# fdc.net
KiCad netlist of a schematic drawn in Altium Designer
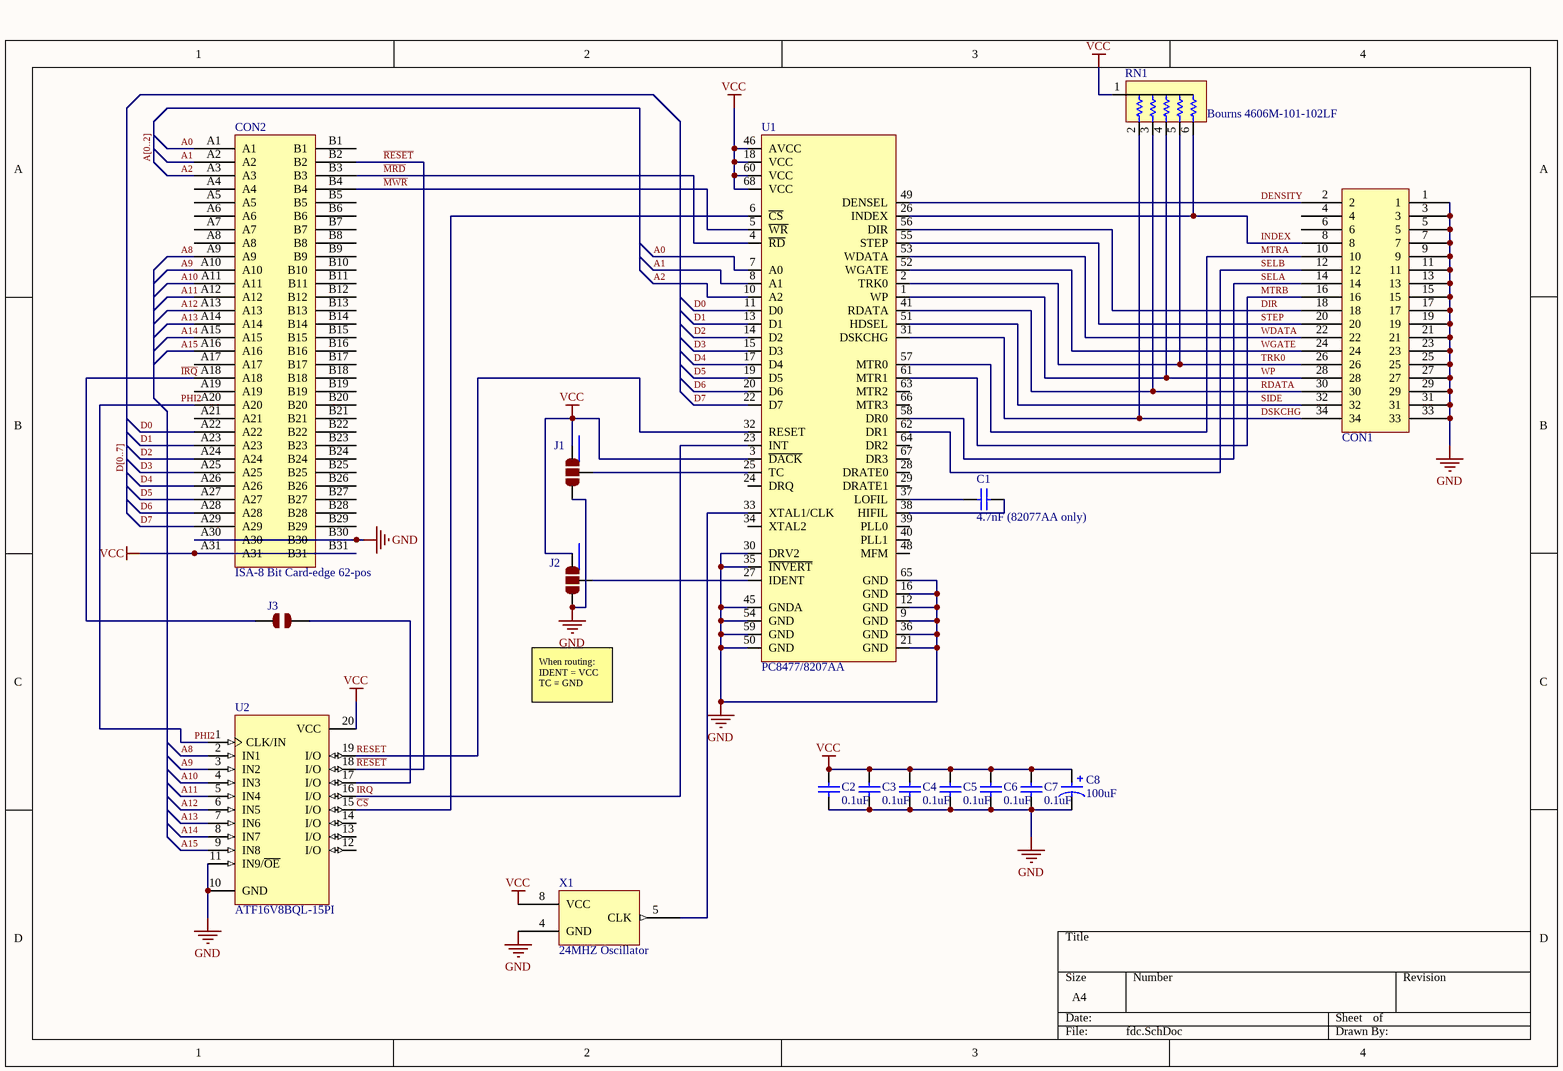
[diagram p0: fdc.SchDoc]

(export (version "E")
  (design (tool "Eeschema 10.0.6"))
  (components
    (comp (ref "C1")
      (value "4.7nF (82077AA only)")
      (footprint "PCB-d10phdktxl02f6vu32bf-1")
      (description "K Series 4.7 nF 50 V ±10 % Tolerance X7R Radial Multilayer Ceramic Capacitor")
      (libsource (lib "CommunityVault") (part "CMP-124134-6"))
    )
    (comp (ref "C2")
      (value "0.1uF")
      (footprint "PCB-gb6o2snpw67z713rrl5r-1")
      (description "Generic Ceramic capacitor")
      (libsource (lib "CommunityVault") (part "CMP-mck1uwszlh1jwp1a4juu-2"))
    )
    (comp (ref "C3")
      (value "0.1uF")
      (footprint "PCB-gb6o2snpw67z713rrl5r-1")
      (description "Generic Ceramic capacitor")
      (libsource (lib "CommunityVault") (part "CMP-mck1uwszlh1jwp1a4juu-2"))
    )
    (comp (ref "C4")
      (value "0.1uF")
      (footprint "PCB-gb6o2snpw67z713rrl5r-1")
      (description "Generic Ceramic capacitor")
      (libsource (lib "CommunityVault") (part "CMP-mck1uwszlh1jwp1a4juu-2"))
    )
    (comp (ref "C5")
      (value "0.1uF")
      (footprint "PCB-gb6o2snpw67z713rrl5r-1")
      (description "Generic Ceramic capacitor")
      (libsource (lib "CommunityVault") (part "CMP-mck1uwszlh1jwp1a4juu-2"))
    )
    (comp (ref "C6")
      (value "0.1uF")
      (footprint "PCB-gb6o2snpw67z713rrl5r-1")
      (description "Generic Ceramic capacitor")
      (libsource (lib "CommunityVault") (part "CMP-mck1uwszlh1jwp1a4juu-2"))
    )
    (comp (ref "C7")
      (value "0.1uF")
      (footprint "PCB-gb6o2snpw67z713rrl5r-1")
      (description "Generic Ceramic capacitor")
      (libsource (lib "CommunityVault") (part "CMP-mck1uwszlh1jwp1a4juu-2"))
    )
    (comp (ref "C8")
      (value "100uF")
      (footprint "PCB-zkzjfh55ek2i5yq9ppya-1")
      (description "Electrolytic capacitor, 2.5mm lead spacing")
      (libsource (lib "FavoritesLibrary") (part "SYM-2ourdj6tgxzh24x23r42-1"))
    )
    (comp (ref "CON1")
      (value "3M N2524-6002RB")
      (footprint "PCB-na3hxtpjg5diai2m4atz-1")
      (description "Header, 4-Wall; Copper Alloy; 200 u in.60/40 Tin/Lead; 2; Black; 0.38 in.; 34")
      (libsource (lib "CommunityVault") (part "CMP-77a2bea8dfe9a865-2"))
    )
    (comp (ref "CON2")
      (value "ISA-8 Bit Card-edge 62-pos")
      (footprint "PCB-2hkdxqdttofatkmr091c-1")
      (description "Card-Edge Male, 62 pos")
      (libsource (lib "CommunityVault") (part "SYM-azy0yq1pw9sh8verv59u-1"))
    )
    (comp (ref "J1")
      (value "Solder Jumper 2-way")
      (footprint "PCB-rrnqmtokqinrd1vbp5jt-1")
      (description "SMD Jumper")
      (libsource (lib "CommunityVault") (part "CMP-0rfjo47dqw9gp5mzow1m-3"))
    )
    (comp (ref "J2")
      (value "Solder Jumper 2-way")
      (footprint "PCB-rrnqmtokqinrd1vbp5jt-1")
      (description "SMD Jumper")
      (libsource (lib "CommunityVault") (part "CMP-0rfjo47dqw9gp5mzow1m-3"))
    )
    (comp (ref "J3")
      (value "SMD Jumper")
      (footprint "PCB-20wha1m7m1debrypqlyx-1")
      (libsource (lib "CommunityVault") (part "SYM-tvx73bcnyo619itupziq-1"))
    )
    (comp (ref "RN1")
      (value "Bourns 4606M-101-102LF")
      (footprint "PCB-6jrb1pmtltsfpt43k1o6-1")
      (description "Res Thick Film NET 1K Ohm 2% 9/10W ±100ppm/°C BUS Conformal 6-Pin SIP Pin Thru-Hole Bulk")
      (fields (field (name "MANUFACTURER PART NUMBER") "4606M-101-102LF"))
      (libsource (lib "FavoritesLibrary") (part "SYM-dbf412e711c10433-1"))
    )
    (comp (ref "U1")
      (value "PC8477/8207AA")
      (footprint "PCB-89xdsse3ufb116eei8ku-1")
      (description "IC Advanced Floppy Ctrlr 68PLCC")
      (libsource (lib "CommunityVault") (part "CMP-e29e2b93411d3d59-3"))
    )
    (comp (ref "U2")
      (value "ATF16V8BQL-15PI")
      (footprint "20P3")
      (description "ATF16V8BQL 5.0V Industry Standard SPLD, 20-lead PDIP, Speed Grade 15, Industrial Grade")
      (libsource (lib "CommunityVault") (part "PLD-ATSPLD-16V8B-IL20"))
    )
    (comp (ref "X1")
      (value "24MHZ Oscillator")
      (footprint "PCB-38wfzuzk5mkmrw5gxtuy-1")
      (description "Generic footprint for Dip-8 Can Oscillator")
      (libsource (lib "FavoritesLibrary") (part "SYM-5f5w4rnabuyvhbl8pua9-1"))
    )
  )
  (nets
    (net (code "1") (name "/A0") (class "Default")
      (node (ref "CON2") (pin "A1") (pinfunction "A1_A1") (pintype "passive"))
      (node (ref "U1") (pin "7") (pinfunction "A0_7") (pintype "passive"))
    )
    (net (code "2") (name "/A1") (class "Default")
      (node (ref "CON2") (pin "A2") (pinfunction "A2_A2") (pintype "passive"))
      (node (ref "U1") (pin "8") (pinfunction "A1_8") (pintype "passive"))
    )
    (net (code "3") (name "/A2") (class "Default")
      (node (ref "CON2") (pin "A3") (pinfunction "A3_A3") (pintype "passive"))
      (node (ref "U1") (pin "10") (pinfunction "A2_10") (pintype "passive"))
    )
    (net (code "4") (name "/A8") (class "Default")
      (node (ref "CON2") (pin "A9") (pinfunction "A9_A9") (pintype "passive"))
      (node (ref "U2") (pin "2") (pinfunction "IN1_2") (pintype "input"))
    )
    (net (code "5") (name "/A9") (class "Default")
      (node (ref "CON2") (pin "A10") (pinfunction "A10_A10") (pintype "passive"))
      (node (ref "U2") (pin "3") (pinfunction "IN2_3") (pintype "input"))
    )
    (net (code "6") (name "/A10") (class "Default")
      (node (ref "CON2") (pin "A11") (pinfunction "A11_A11") (pintype "passive"))
      (node (ref "U2") (pin "4") (pinfunction "IN3_4") (pintype "input"))
    )
    (net (code "7") (name "/A11") (class "Default")
      (node (ref "CON2") (pin "A12") (pinfunction "A12_A12") (pintype "passive"))
      (node (ref "U2") (pin "5") (pinfunction "IN4_5") (pintype "input"))
    )
    (net (code "8") (name "/A12") (class "Default")
      (node (ref "CON2") (pin "A13") (pinfunction "A13_A13") (pintype "passive"))
      (node (ref "U2") (pin "6") (pinfunction "IN5_6") (pintype "input"))
    )
    (net (code "9") (name "/A13") (class "Default")
      (node (ref "CON2") (pin "A14") (pinfunction "A14_A14") (pintype "passive"))
      (node (ref "U2") (pin "7") (pinfunction "IN6_7") (pintype "input"))
    )
    (net (code "10") (name "/A14") (class "Default")
      (node (ref "CON2") (pin "A15") (pinfunction "A15_A15") (pintype "passive"))
      (node (ref "U2") (pin "8") (pinfunction "IN7_8") (pintype "input"))
    )
    (net (code "11") (name "/A15") (class "Default")
      (node (ref "CON2") (pin "A16") (pinfunction "A16_A16") (pintype "passive"))
      (node (ref "U2") (pin "9") (pinfunction "IN8_9") (pintype "input"))
    )
    (net (code "13") (name "/D0") (class "Default")
      (node (ref "CON2") (pin "A22") (pinfunction "A22_A22") (pintype "passive"))
      (node (ref "U1") (pin "11") (pinfunction "D0_11") (pintype "passive"))
    )
    (net (code "14") (name "/D1") (class "Default")
      (node (ref "CON2") (pin "A23") (pinfunction "A23_A23") (pintype "passive"))
      (node (ref "U1") (pin "13") (pinfunction "D1_13") (pintype "passive"))
    )
    (net (code "15") (name "/D2") (class "Default")
      (node (ref "CON2") (pin "A24") (pinfunction "A24_A24") (pintype "passive"))
      (node (ref "U1") (pin "14") (pinfunction "D2_14") (pintype "passive"))
    )
    (net (code "16") (name "/D3") (class "Default")
      (node (ref "CON2") (pin "A25") (pinfunction "A25_A25") (pintype "passive"))
      (node (ref "U1") (pin "15") (pinfunction "D3_15") (pintype "passive"))
    )
    (net (code "17") (name "/D4") (class "Default")
      (node (ref "CON2") (pin "A26") (pinfunction "A26_A26") (pintype "passive"))
      (node (ref "U1") (pin "17") (pinfunction "D4_17") (pintype "passive"))
    )
    (net (code "18") (name "/D5") (class "Default")
      (node (ref "CON2") (pin "A27") (pinfunction "A27_A27") (pintype "passive"))
      (node (ref "U1") (pin "19") (pinfunction "D5_19") (pintype "passive"))
    )
    (net (code "19") (name "/D6") (class "Default")
      (node (ref "CON2") (pin "A28") (pinfunction "A28_A28") (pintype "passive"))
      (node (ref "U1") (pin "20") (pinfunction "D6_20") (pintype "passive"))
    )
    (net (code "20") (name "/D7") (class "Default")
      (node (ref "CON2") (pin "A29") (pinfunction "A29_A29") (pintype "passive"))
      (node (ref "U1") (pin "22") (pinfunction "D7_22") (pintype "passive"))
    )
    (net (code "21") (name "/DENSITY") (class "Default")
      (node (ref "CON1") (pin "2") (pinfunction "2_2") (pintype "passive"))
      (node (ref "U1") (pin "49") (pinfunction "DENSEL_49") (pintype "passive"))
    )
    (net (code "22") (name "/DIR") (class "Default")
      (node (ref "CON1") (pin "18") (pinfunction "18_18") (pintype "passive"))
      (node (ref "U1") (pin "56") (pinfunction "DIR_56") (pintype "passive"))
    )
    (net (code "23") (name "/DSKCHG") (class "Default")
      (node (ref "CON1") (pin "34") (pinfunction "34_34") (pintype "passive"))
      (node (ref "RN1") (pin "2") (pinfunction "2_2") (pintype "passive"))
      (node (ref "U1") (pin "31") (pinfunction "DSKCHG_31") (pintype "passive"))
    )
    (net (code "25") (name "/INDEX") (class "Default")
      (node (ref "CON1") (pin "8") (pinfunction "8_8") (pintype "passive"))
      (node (ref "RN1") (pin "6") (pinfunction "6_6") (pintype "passive"))
      (node (ref "U1") (pin "26") (pinfunction "INDEX_26") (pintype "passive"))
    )
    (net (code "26") (name "/IRQ") (class "Default")
      (node (ref "U1") (pin "23") (pinfunction "INT_23") (pintype "passive"))
      (node (ref "U2") (pin "16") (pinfunction "I/O_16") (pintype "bidirectional"))
    )
    (net (code "27") (name "/MTRA") (class "Default")
      (node (ref "CON1") (pin "10") (pinfunction "10_10") (pintype "passive"))
      (node (ref "U1") (pin "57") (pinfunction "MTR0_57") (pintype "passive"))
    )
    (net (code "28") (name "/MTRB") (class "Default")
      (node (ref "CON1") (pin "16") (pinfunction "16_16") (pintype "passive"))
      (node (ref "U1") (pin "61") (pinfunction "MTR1_61") (pintype "passive"))
    )
    (net (code "29") (name "/PHI2") (class "Default")
      (node (ref "CON2") (pin "A20") (pinfunction "A20_A20") (pintype "passive"))
      (node (ref "U2") (pin "1") (pinfunction "CLK/IN_1") (pintype "input"))
    )
    (net (code "30") (name "/RDATA") (class "Default")
      (node (ref "CON1") (pin "30") (pinfunction "30_30") (pintype "passive"))
      (node (ref "RN1") (pin "3") (pinfunction "3_3") (pintype "passive"))
      (node (ref "U1") (pin "41") (pinfunction "RDATA_41") (pintype "passive"))
    )
    (net (code "31") (name "/RESET") (class "Default")
      (node (ref "U1") (pin "32") (pinfunction "RESET_32") (pintype "passive"))
      (node (ref "U2") (pin "19") (pinfunction "I/O_19") (pintype "bidirectional"))
    )
    (net (code "32") (name "/SELA") (class "Default")
      (node (ref "CON1") (pin "14") (pinfunction "14_14") (pintype "passive"))
      (node (ref "U1") (pin "58") (pinfunction "DR0_58") (pintype "passive"))
    )
    (net (code "33") (name "/SELB") (class "Default")
      (node (ref "CON1") (pin "12") (pinfunction "12_12") (pintype "passive"))
      (node (ref "U1") (pin "62") (pinfunction "DR1_62") (pintype "passive"))
    )
    (net (code "34") (name "/SIDE") (class "Default")
      (node (ref "CON1") (pin "32") (pinfunction "32_32") (pintype "passive"))
      (node (ref "U1") (pin "51") (pinfunction "HDSEL_51") (pintype "passive"))
    )
    (net (code "35") (name "/STEP") (class "Default")
      (node (ref "CON1") (pin "20") (pinfunction "20_20") (pintype "passive"))
      (node (ref "U1") (pin "55") (pinfunction "STEP_55") (pintype "passive"))
    )
    (net (code "36") (name "/TRK0") (class "Default")
      (node (ref "CON1") (pin "26") (pinfunction "26_26") (pintype "passive"))
      (node (ref "RN1") (pin "5") (pinfunction "5_5") (pintype "passive"))
      (node (ref "U1") (pin "2") (pinfunction "TRK0_2") (pintype "passive"))
    )
    (net (code "37") (name "/WDATA") (class "Default")
      (node (ref "CON1") (pin "22") (pinfunction "22_22") (pintype "passive"))
      (node (ref "U1") (pin "53") (pinfunction "WDATA_53") (pintype "passive"))
    )
    (net (code "38") (name "/WGATE") (class "Default")
      (node (ref "CON1") (pin "24") (pinfunction "24_24") (pintype "passive"))
      (node (ref "U1") (pin "52") (pinfunction "WGATE_52") (pintype "passive"))
    )
    (net (code "39") (name "/WP") (class "Default")
      (node (ref "CON1") (pin "28") (pinfunction "28_28") (pintype "passive"))
      (node (ref "RN1") (pin "4") (pinfunction "4_4") (pintype "passive"))
      (node (ref "U1") (pin "1") (pinfunction "WP_1") (pintype "passive"))
    )
    (net (code "40") (name "/~{CS}") (class "Default")
      (node (ref "U1") (pin "6") (pinfunction "~{CS}_6") (pintype "passive"))
      (node (ref "U2") (pin "15") (pinfunction "I/O_15") (pintype "bidirectional"))
    )
    (net (code "41") (name "/~{IRQ}") (class "Default")
      (node (ref "CON2") (pin "A18") (pinfunction "A18_A18") (pintype "passive"))
      (node (ref "J3") (pin "1") (pinfunction "1_1") (pintype "passive"))
    )
    (net (code "42") (name "/~{MRD}") (class "Default")
      (node (ref "CON2") (pin "B3") (pinfunction "B3_B3") (pintype "passive"))
      (node (ref "U1") (pin "4") (pinfunction "~{RD}_4") (pintype "passive"))
    )
    (net (code "43") (name "/~{MWR}") (class "Default")
      (node (ref "CON2") (pin "B4") (pinfunction "B4_B4") (pintype "passive"))
      (node (ref "U1") (pin "5") (pinfunction "~{WR}_5") (pintype "passive"))
    )
    (net (code "44") (name "/~{RESET}") (class "Default")
      (node (ref "CON2") (pin "B2") (pinfunction "B2_B2") (pintype "passive"))
      (node (ref "U2") (pin "18") (pinfunction "I/O_18") (pintype "bidirectional"))
    )
    (net (code "45") (name "GND") (class "Default")
      (node (ref "C2") (pin "1") (pinfunction "1_1") (pintype "passive"))
      (node (ref "C3") (pin "1") (pinfunction "1_1") (pintype "passive"))
      (node (ref "C4") (pin "1") (pinfunction "1_1") (pintype "passive"))
      (node (ref "C5") (pin "1") (pinfunction "1_1") (pintype "passive"))
      (node (ref "C6") (pin "1") (pinfunction "1_1") (pintype "passive"))
      (node (ref "C7") (pin "1") (pinfunction "1_1") (pintype "passive"))
      (node (ref "C8") (pin "2") (pinfunction "2_2") (pintype "passive"))
      (node (ref "CON1") (pin "1") (pinfunction "1_1") (pintype "passive"))
      (node (ref "CON1") (pin "11") (pinfunction "11_11") (pintype "passive"))
      (node (ref "CON1") (pin "13") (pinfunction "13_13") (pintype "passive"))
      (node (ref "CON1") (pin "15") (pinfunction "15_15") (pintype "passive"))
      (node (ref "CON1") (pin "17") (pinfunction "17_17") (pintype "passive"))
      (node (ref "CON1") (pin "19") (pinfunction "19_19") (pintype "passive"))
      (node (ref "CON1") (pin "21") (pinfunction "21_21") (pintype "passive"))
      (node (ref "CON1") (pin "23") (pinfunction "23_23") (pintype "passive"))
      (node (ref "CON1") (pin "25") (pinfunction "25_25") (pintype "passive"))
      (node (ref "CON1") (pin "27") (pinfunction "27_27") (pintype "passive"))
      (node (ref "CON1") (pin "29") (pinfunction "29_29") (pintype "passive"))
      (node (ref "CON1") (pin "3") (pinfunction "3_3") (pintype "passive"))
      (node (ref "CON1") (pin "31") (pinfunction "31_31") (pintype "passive"))
      (node (ref "CON1") (pin "33") (pinfunction "33_33") (pintype "passive"))
      (node (ref "CON1") (pin "5") (pinfunction "5_5") (pintype "passive"))
      (node (ref "CON1") (pin "7") (pinfunction "7_7") (pintype "passive"))
      (node (ref "CON1") (pin "9") (pinfunction "9_9") (pintype "passive"))
      (node (ref "CON2") (pin "A30") (pinfunction "A30_A30") (pintype "passive"))
      (node (ref "CON2") (pin "B30") (pinfunction "B30_B30") (pintype "passive"))
      (node (ref "J1") (pin "3") (pinfunction "3_3") (pintype "passive"))
      (node (ref "J2") (pin "3") (pinfunction "3_3") (pintype "passive"))
      (node (ref "U1") (pin "12") (pinfunction "GND_12") (pintype "passive"))
      (node (ref "U1") (pin "16") (pinfunction "GND_16") (pintype "passive"))
      (node (ref "U1") (pin "21") (pinfunction "GND_21") (pintype "passive"))
      (node (ref "U1") (pin "30") (pinfunction "DRV2_30") (pintype "passive"))
      (node (ref "U1") (pin "35") (pinfunction "~{INVERT}_35") (pintype "passive"))
      (node (ref "U1") (pin "36") (pinfunction "GND_36") (pintype "passive"))
      (node (ref "U1") (pin "45") (pinfunction "GNDA_45") (pintype "passive"))
      (node (ref "U1") (pin "50") (pinfunction "GND_50") (pintype "passive"))
      (node (ref "U1") (pin "54") (pinfunction "GND_54") (pintype "passive"))
      (node (ref "U1") (pin "59") (pinfunction "GND_59") (pintype "passive"))
      (node (ref "U1") (pin "65") (pinfunction "GND_65") (pintype "passive"))
      (node (ref "U1") (pin "9") (pinfunction "GND_9") (pintype "passive"))
      (node (ref "U2") (pin "10") (pinfunction "GND_10") (pintype "power_in"))
      (node (ref "U2") (pin "11") (pinfunction "IN9/~{OE}_11") (pintype "input"))
      (node (ref "X1") (pin "4") (pinfunction "GND_4") (pintype "power_in"))
    )
    (net (code "46") (name "Net-(J3-Pad2)") (class "Default")
      (node (ref "J3") (pin "2") (pinfunction "2_2") (pintype "passive"))
      (node (ref "U2") (pin "17") (pinfunction "I/O_17") (pintype "bidirectional"))
    )
    (net (code "47") (name "Net-(U1-HIFIL)") (class "Default")
      (node (ref "C1") (pin "2") (pinfunction "2_2") (pintype "passive"))
      (node (ref "U1") (pin "38") (pinfunction "HIFIL_38") (pintype "passive"))
    )
    (net (code "48") (name "Net-(U1-IDENT)") (class "Default")
      (node (ref "J2") (pin "2") (pinfunction "2_2") (pintype "passive"))
      (node (ref "U1") (pin "27") (pinfunction "IDENT_27") (pintype "passive"))
    )
    (net (code "49") (name "Net-(U1-LOFIL)") (class "Default")
      (node (ref "C1") (pin "1") (pinfunction "1_1") (pintype "passive"))
      (node (ref "U1") (pin "37") (pinfunction "LOFIL_37") (pintype "passive"))
    )
    (net (code "50") (name "Net-(U1-TC)") (class "Default")
      (node (ref "J1") (pin "2") (pinfunction "2_2") (pintype "passive"))
      (node (ref "U1") (pin "25") (pinfunction "TC_25") (pintype "passive"))
    )
    (net (code "51") (name "Net-(U1-XTAL1{slash}CLK)") (class "Default")
      (node (ref "U1") (pin "33") (pinfunction "XTAL1/CLK_33") (pintype "passive"))
      (node (ref "X1") (pin "5") (pinfunction "CLK_5") (pintype "output"))
    )
    (net (code "52") (name "VCC") (class "Default")
      (node (ref "C2") (pin "2") (pinfunction "2_2") (pintype "passive"))
      (node (ref "C3") (pin "2") (pinfunction "2_2") (pintype "passive"))
      (node (ref "C4") (pin "2") (pinfunction "2_2") (pintype "passive"))
      (node (ref "C5") (pin "2") (pinfunction "2_2") (pintype "passive"))
      (node (ref "C6") (pin "2") (pinfunction "2_2") (pintype "passive"))
      (node (ref "C7") (pin "2") (pinfunction "2_2") (pintype "passive"))
      (node (ref "C8") (pin "1") (pinfunction "1_1") (pintype "passive"))
      (node (ref "CON2") (pin "A31") (pinfunction "A31_A31") (pintype "passive"))
      (node (ref "CON2") (pin "B31") (pinfunction "B31_B31") (pintype "passive"))
      (node (ref "J1") (pin "1") (pinfunction "1_1") (pintype "passive"))
      (node (ref "J2") (pin "1") (pinfunction "1_1") (pintype "passive"))
      (node (ref "RN1") (pin "1") (pinfunction "1_1") (pintype "passive"))
      (node (ref "U1") (pin "18") (pinfunction "VCC_18") (pintype "passive"))
      (node (ref "U1") (pin "3") (pinfunction "~{DACK}_3") (pintype "passive"))
      (node (ref "U1") (pin "46") (pinfunction "AVCC_46") (pintype "passive"))
      (node (ref "U1") (pin "60") (pinfunction "VCC_60") (pintype "passive"))
      (node (ref "U1") (pin "68") (pinfunction "VCC_68") (pintype "passive"))
      (node (ref "U2") (pin "20") (pinfunction "VCC_20") (pintype "power_in"))
      (node (ref "X1") (pin "8") (pinfunction "VCC_8") (pintype "power_in"))
    )
    (net (code "53") (name "unconnected-(CON1-Pad4)") (class "Default")
      (node (ref "CON1") (pin "4") (pinfunction "4_4") (pintype "passive"))
    )
    (net (code "54") (name "unconnected-(CON1-Pad6)") (class "Default")
      (node (ref "CON1") (pin "6") (pinfunction "6_6") (pintype "passive"))
    )
    (net (code "55") (name "unconnected-(CON2-PadA4)") (class "Default")
      (node (ref "CON2") (pin "A4") (pinfunction "A4_A4") (pintype "passive"))
    )
    (net (code "56") (name "unconnected-(CON2-PadA5)") (class "Default")
      (node (ref "CON2") (pin "A5") (pinfunction "A5_A5") (pintype "passive"))
    )
    (net (code "57") (name "unconnected-(CON2-PadA6)") (class "Default")
      (node (ref "CON2") (pin "A6") (pinfunction "A6_A6") (pintype "passive"))
    )
    (net (code "58") (name "unconnected-(CON2-PadA7)") (class "Default")
      (node (ref "CON2") (pin "A7") (pinfunction "A7_A7") (pintype "passive"))
    )
    (net (code "59") (name "unconnected-(CON2-PadA8)") (class "Default")
      (node (ref "CON2") (pin "A8") (pinfunction "A8_A8") (pintype "passive"))
    )
    (net (code "60") (name "unconnected-(CON2-PadA17)") (class "Default")
      (node (ref "CON2") (pin "A17") (pinfunction "A17_A17") (pintype "passive"))
    )
    (net (code "61") (name "unconnected-(CON2-PadA19)") (class "Default")
      (node (ref "CON2") (pin "A19") (pinfunction "A19_A19") (pintype "passive"))
    )
    (net (code "62") (name "unconnected-(CON2-PadA21)") (class "Default")
      (node (ref "CON2") (pin "A21") (pinfunction "A21_A21") (pintype "passive"))
    )
    (net (code "63") (name "unconnected-(CON2-PadB1)") (class "Default")
      (node (ref "CON2") (pin "B1") (pinfunction "B1_B1") (pintype "passive"))
    )
    (net (code "64") (name "unconnected-(CON2-PadB5)") (class "Default")
      (node (ref "CON2") (pin "B5") (pinfunction "B5_B5") (pintype "passive"))
    )
    (net (code "65") (name "unconnected-(CON2-PadB6)") (class "Default")
      (node (ref "CON2") (pin "B6") (pinfunction "B6_B6") (pintype "passive"))
    )
    (net (code "66") (name "unconnected-(CON2-PadB7)") (class "Default")
      (node (ref "CON2") (pin "B7") (pinfunction "B7_B7") (pintype "passive"))
    )
    (net (code "67") (name "unconnected-(CON2-PadB8)") (class "Default")
      (node (ref "CON2") (pin "B8") (pinfunction "B8_B8") (pintype "passive"))
    )
    (net (code "68") (name "unconnected-(CON2-PadB9)") (class "Default")
      (node (ref "CON2") (pin "B9") (pinfunction "B9_B9") (pintype "passive"))
    )
    (net (code "69") (name "unconnected-(CON2-PadB10)") (class "Default")
      (node (ref "CON2") (pin "B10") (pinfunction "B10_B10") (pintype "passive"))
    )
    (net (code "70") (name "unconnected-(CON2-PadB11)") (class "Default")
      (node (ref "CON2") (pin "B11") (pinfunction "B11_B11") (pintype "passive"))
    )
    (net (code "71") (name "unconnected-(CON2-PadB12)") (class "Default")
      (node (ref "CON2") (pin "B12") (pinfunction "B12_B12") (pintype "passive"))
    )
    (net (code "72") (name "unconnected-(CON2-PadB13)") (class "Default")
      (node (ref "CON2") (pin "B13") (pinfunction "B13_B13") (pintype "passive"))
    )
    (net (code "73") (name "unconnected-(CON2-PadB14)") (class "Default")
      (node (ref "CON2") (pin "B14") (pinfunction "B14_B14") (pintype "passive"))
    )
    (net (code "74") (name "unconnected-(CON2-PadB15)") (class "Default")
      (node (ref "CON2") (pin "B15") (pinfunction "B15_B15") (pintype "passive"))
    )
    (net (code "75") (name "unconnected-(CON2-PadB16)") (class "Default")
      (node (ref "CON2") (pin "B16") (pinfunction "B16_B16") (pintype "passive"))
    )
    (net (code "76") (name "unconnected-(CON2-PadB17)") (class "Default")
      (node (ref "CON2") (pin "B17") (pinfunction "B17_B17") (pintype "passive"))
    )
    (net (code "77") (name "unconnected-(CON2-PadB18)") (class "Default")
      (node (ref "CON2") (pin "B18") (pinfunction "B18_B18") (pintype "passive"))
    )
    (net (code "78") (name "unconnected-(CON2-PadB19)") (class "Default")
      (node (ref "CON2") (pin "B19") (pinfunction "B19_B19") (pintype "passive"))
    )
    (net (code "79") (name "unconnected-(CON2-PadB20)") (class "Default")
      (node (ref "CON2") (pin "B20") (pinfunction "B20_B20") (pintype "passive"))
    )
    (net (code "80") (name "unconnected-(CON2-PadB21)") (class "Default")
      (node (ref "CON2") (pin "B21") (pinfunction "B21_B21") (pintype "passive"))
    )
    (net (code "81") (name "unconnected-(CON2-PadB22)") (class "Default")
      (node (ref "CON2") (pin "B22") (pinfunction "B22_B22") (pintype "passive"))
    )
    (net (code "82") (name "unconnected-(CON2-PadB23)") (class "Default")
      (node (ref "CON2") (pin "B23") (pinfunction "B23_B23") (pintype "passive"))
    )
    (net (code "83") (name "unconnected-(CON2-PadB24)") (class "Default")
      (node (ref "CON2") (pin "B24") (pinfunction "B24_B24") (pintype "passive"))
    )
    (net (code "84") (name "unconnected-(CON2-PadB25)") (class "Default")
      (node (ref "CON2") (pin "B25") (pinfunction "B25_B25") (pintype "passive"))
    )
    (net (code "85") (name "unconnected-(CON2-PadB26)") (class "Default")
      (node (ref "CON2") (pin "B26") (pinfunction "B26_B26") (pintype "passive"))
    )
    (net (code "86") (name "unconnected-(CON2-PadB27)") (class "Default")
      (node (ref "CON2") (pin "B27") (pinfunction "B27_B27") (pintype "passive"))
    )
    (net (code "87") (name "unconnected-(CON2-PadB28)") (class "Default")
      (node (ref "CON2") (pin "B28") (pinfunction "B28_B28") (pintype "passive"))
    )
    (net (code "88") (name "unconnected-(CON2-PadB29)") (class "Default")
      (node (ref "CON2") (pin "B29") (pinfunction "B29_B29") (pintype "passive"))
    )
    (net (code "89") (name "unconnected-(U1-DR2-Pad64)") (class "Default")
      (node (ref "U1") (pin "64") (pinfunction "DR2_64") (pintype "passive"))
    )
    (net (code "90") (name "unconnected-(U1-DR3-Pad67)") (class "Default")
      (node (ref "U1") (pin "67") (pinfunction "DR3_67") (pintype "passive"))
    )
    (net (code "91") (name "unconnected-(U1-DRATE0-Pad28)") (class "Default")
      (node (ref "U1") (pin "28") (pinfunction "DRATE0_28") (pintype "passive"))
    )
    (net (code "92") (name "unconnected-(U1-DRATE1-Pad29)") (class "Default")
      (node (ref "U1") (pin "29") (pinfunction "DRATE1_29") (pintype "passive"))
    )
    (net (code "93") (name "unconnected-(U1-DRQ-Pad24)") (class "Default")
      (node (ref "U1") (pin "24") (pinfunction "DRQ_24") (pintype "passive"))
    )
    (net (code "94") (name "unconnected-(U1-MFM-Pad48)") (class "Default")
      (node (ref "U1") (pin "48") (pinfunction "MFM_48") (pintype "passive"))
    )
    (net (code "95") (name "unconnected-(U1-MTR2-Pad63)") (class "Default")
      (node (ref "U1") (pin "63") (pinfunction "MTR2_63") (pintype "passive"))
    )
    (net (code "96") (name "unconnected-(U1-MTR3-Pad66)") (class "Default")
      (node (ref "U1") (pin "66") (pinfunction "MTR3_66") (pintype "passive"))
    )
    (net (code "97") (name "unconnected-(U1-NC-Pad42)") (class "Default")
      (node (ref "U1") (pin "42") (pinfunction "NC_42") (pintype "passive"))
    )
    (net (code "98") (name "unconnected-(U1-NC-Pad43)") (class "Default")
      (node (ref "U1") (pin "43") (pinfunction "NC_43") (pintype "passive"))
    )
    (net (code "99") (name "unconnected-(U1-NC-Pad44)") (class "Default")
      (node (ref "U1") (pin "44") (pinfunction "NC_44") (pintype "passive"))
    )
    (net (code "100") (name "unconnected-(U1-NC-Pad47)") (class "Default")
      (node (ref "U1") (pin "47") (pinfunction "NC_47") (pintype "passive"))
    )
    (net (code "101") (name "unconnected-(U1-PLL0-Pad39)") (class "Default")
      (node (ref "U1") (pin "39") (pinfunction "PLL0_39") (pintype "passive"))
    )
    (net (code "102") (name "unconnected-(U1-PLL1-Pad40)") (class "Default")
      (node (ref "U1") (pin "40") (pinfunction "PLL1_40") (pintype "passive"))
    )
    (net (code "103") (name "unconnected-(U1-XTAL2-Pad34)") (class "Default")
      (node (ref "U1") (pin "34") (pinfunction "XTAL2_34") (pintype "passive"))
    )
    (net (code "104") (name "unconnected-(U2-I{slash}O-Pad12)") (class "Default")
      (node (ref "U2") (pin "12") (pinfunction "I/O_12") (pintype "bidirectional"))
    )
    (net (code "105") (name "unconnected-(U2-I{slash}O-Pad13)") (class "Default")
      (node (ref "U2") (pin "13") (pinfunction "I/O_13") (pintype "bidirectional"))
    )
    (net (code "106") (name "unconnected-(U2-I{slash}O-Pad14)") (class "Default")
      (node (ref "U2") (pin "14") (pinfunction "I/O_14") (pintype "bidirectional"))
    )
  )
)
